# jd9_redraw.net
KiCad netlist of a schematic drawn in EAGLE
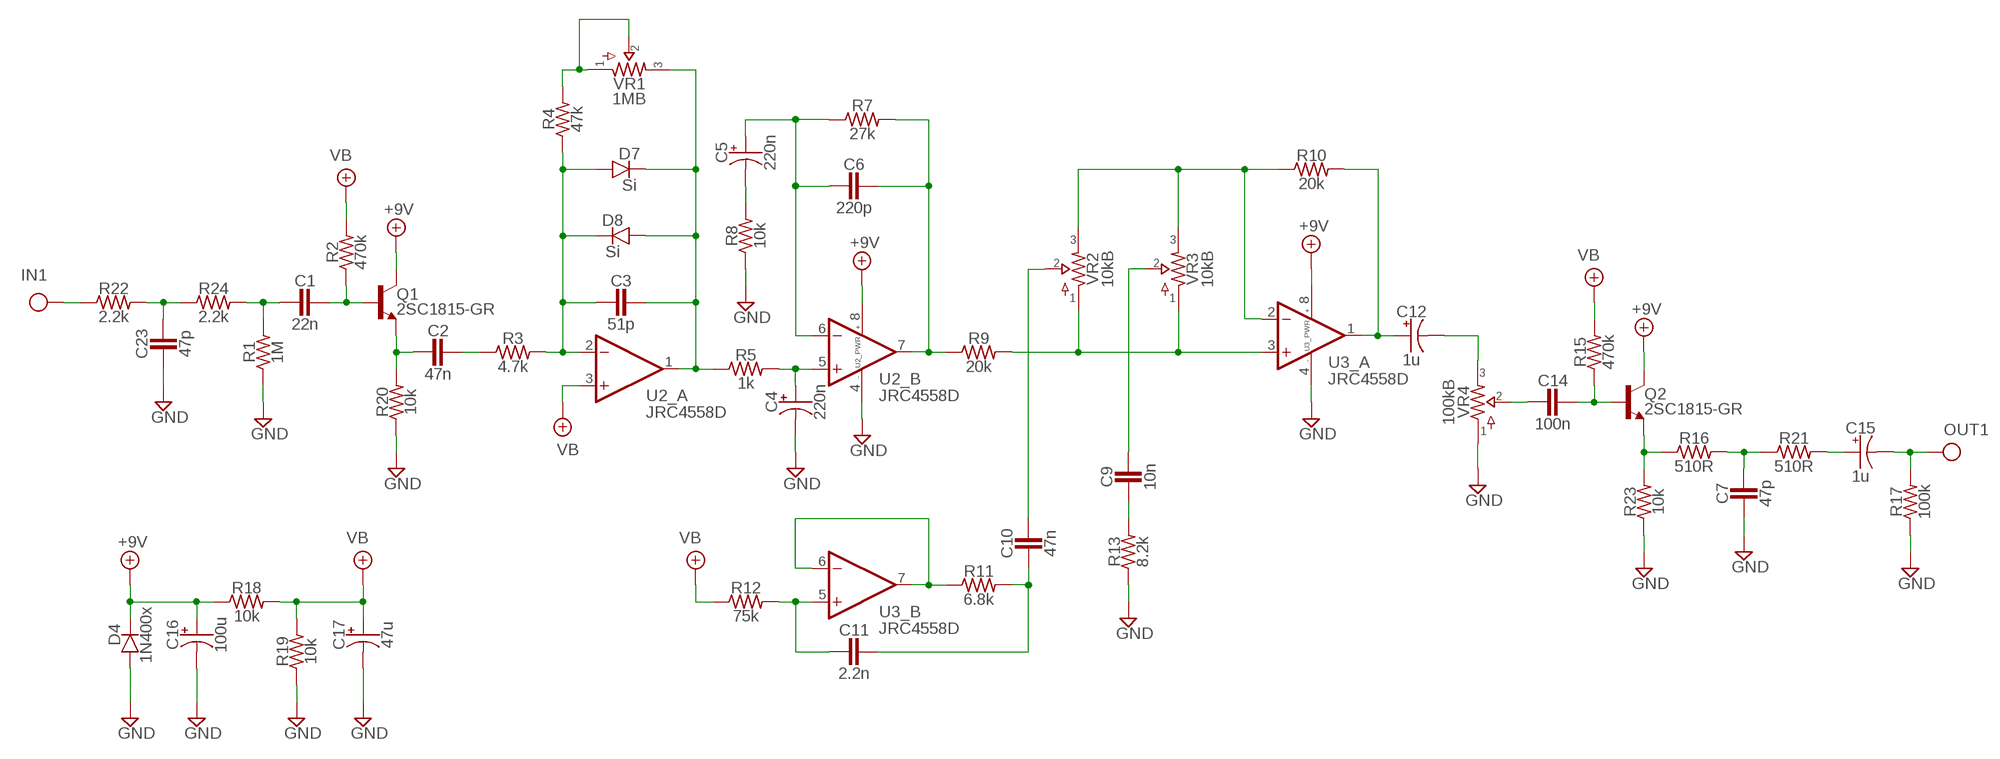
[diagram p0: schematic, sheet 1]

(export (version "E")
  (design (tool "Eeschema 10.0.6"))
  (components
    (comp (ref "C1")
      (value "22n")
      (footprint "eagle-import:BOX_SMALL")
      (libsource (lib "eagle-import") (part "CER/FILMBOX.1"))
    )
    (comp (ref "C2")
      (value "47n")
      (footprint "eagle-import:BOX_SMALL")
      (libsource (lib "eagle-import") (part "CER/FILMBOX.1"))
    )
    (comp (ref "C3")
      (value "51p")
      (footprint "eagle-import:BOX_SMALL")
      (libsource (lib "eagle-import") (part "CER/FILMBOX.1"))
    )
    (comp (ref "C4")
      (value "220n")
      (footprint "eagle-import:050_020")
      (libsource (lib "eagle-import") (part "0500"))
    )
    (comp (ref "C5")
      (value "220n")
      (footprint "eagle-import:050_020")
      (libsource (lib "eagle-import") (part "0500"))
    )
    (comp (ref "C6")
      (value "220p")
      (footprint "eagle-import:BOX_SMALL")
      (libsource (lib "eagle-import") (part "CER/FILMBOX.1"))
    )
    (comp (ref "C7")
      (value "47p")
      (footprint "eagle-import:BOX_SMALL")
      (libsource (lib "eagle-import") (part "CER/FILMBOX.1"))
    )
    (comp (ref "C9")
      (value "10n")
      (footprint "eagle-import:BOX_SMALL")
      (libsource (lib "eagle-import") (part "CER/FILMBOX.1"))
    )
    (comp (ref "C10")
      (value "47n")
      (footprint "eagle-import:BOX_SMALL")
      (libsource (lib "eagle-import") (part "CER/FILMBOX.1"))
    )
    (comp (ref "C11")
      (value "2.2n")
      (footprint "eagle-import:BOX_SMALL")
      (libsource (lib "eagle-import") (part "CER/FILMBOX.1"))
    )
    (comp (ref "C12")
      (value "1u")
      (footprint "eagle-import:050_020")
      (libsource (lib "eagle-import") (part "0500"))
    )
    (comp (ref "C14")
      (value "100n")
      (footprint "eagle-import:BOX_SMALL")
      (libsource (lib "eagle-import") (part "CER/FILMBOX.1"))
    )
    (comp (ref "C15")
      (value "1u")
      (footprint "eagle-import:050_020")
      (libsource (lib "eagle-import") (part "0500"))
    )
    (comp (ref "C16")
      (value "100u")
      (footprint "eagle-import:050_020")
      (libsource (lib "eagle-import") (part "0500"))
    )
    (comp (ref "C17")
      (value "47u")
      (footprint "eagle-import:050_020")
      (libsource (lib "eagle-import") (part "0500"))
    )
    (comp (ref "C23")
      (value "47p")
      (footprint "eagle-import:BOX_SMALL")
      (libsource (lib "eagle-import") (part "CER/FILMBOX.1"))
    )
    (comp (ref "D4")
      (value "1N400x")
      (footprint "eagle-import:DO41-2")
      (libsource (lib "eagle-import") (part "DO41.2"))
    )
    (comp (ref "D7")
      (value "Si")
      (footprint "eagle-import:DO35-2")
      (libsource (lib "eagle-import") (part "DO35.2"))
    )
    (comp (ref "D8")
      (value "Si")
      (footprint "eagle-import:DO35-2")
      (libsource (lib "eagle-import") (part "DO35.2"))
    )
    (comp (ref "Q1")
      (value "2SC1815-GR")
      (footprint "eagle-import:TO92-")
      (libsource (lib "eagle-import") (part "2N3904"))
    )
    (comp (ref "Q2")
      (value "2SC1815-GR")
      (footprint "eagle-import:TO92-")
      (libsource (lib "eagle-import") (part "2N3904"))
    )
    (comp (ref "R1")
      (value "1M")
      (footprint "eagle-import:R0207_3")
      (libsource (lib "eagle-import") (part "R_.3B"))
    )
    (comp (ref "R2")
      (value "470k")
      (footprint "eagle-import:R0207_3")
      (libsource (lib "eagle-import") (part "R_.3B"))
    )
    (comp (ref "R3")
      (value "4.7k")
      (footprint "eagle-import:R0207_3")
      (libsource (lib "eagle-import") (part "R_.3B"))
    )
    (comp (ref "R4")
      (value "47k")
      (footprint "eagle-import:R0207_3")
      (libsource (lib "eagle-import") (part "R_.3B"))
    )
    (comp (ref "R5")
      (value "1k")
      (footprint "eagle-import:R0207_3")
      (libsource (lib "eagle-import") (part "R_.3B"))
    )
    (comp (ref "R7")
      (value "27k")
      (footprint "eagle-import:R0207_3")
      (libsource (lib "eagle-import") (part "R_.3B"))
    )
    (comp (ref "R8")
      (value "10k")
      (footprint "eagle-import:R0207_3")
      (libsource (lib "eagle-import") (part "R_.3B"))
    )
    (comp (ref "R9")
      (value "20k")
      (footprint "eagle-import:R0207_3")
      (libsource (lib "eagle-import") (part "R_.3B"))
    )
    (comp (ref "R10")
      (value "20k")
      (footprint "eagle-import:R0207_3")
      (libsource (lib "eagle-import") (part "R_.3B"))
    )
    (comp (ref "R11")
      (value "6.8k")
      (footprint "eagle-import:R0207_3")
      (libsource (lib "eagle-import") (part "R_.3B"))
    )
    (comp (ref "R12")
      (value "75k")
      (footprint "eagle-import:R0207_3")
      (libsource (lib "eagle-import") (part "R_.3B"))
    )
    (comp (ref "R13")
      (value "8.2k")
      (footprint "eagle-import:R0207_3")
      (libsource (lib "eagle-import") (part "R_.3B"))
    )
    (comp (ref "R15")
      (value "470k")
      (footprint "eagle-import:R0207_3")
      (libsource (lib "eagle-import") (part "R_.3B"))
    )
    (comp (ref "R16")
      (value "510R")
      (footprint "eagle-import:R0207_3")
      (libsource (lib "eagle-import") (part "R_.3B"))
    )
    (comp (ref "R17")
      (value "100k")
      (footprint "eagle-import:R0207_3")
      (libsource (lib "eagle-import") (part "R_.3B"))
    )
    (comp (ref "R18")
      (value "10k")
      (footprint "eagle-import:R0207_3")
      (libsource (lib "eagle-import") (part "R_.3B"))
    )
    (comp (ref "R19")
      (value "10k")
      (footprint "eagle-import:R0207_3")
      (libsource (lib "eagle-import") (part "R_.3B"))
    )
    (comp (ref "R20")
      (value "10k")
      (footprint "eagle-import:R0207_3")
      (libsource (lib "eagle-import") (part "R_.3B"))
    )
    (comp (ref "R21")
      (value "510R")
      (footprint "eagle-import:R0207_3")
      (libsource (lib "eagle-import") (part "R_.3B"))
    )
    (comp (ref "R22")
      (value "2.2k")
      (footprint "eagle-import:R0207_3")
      (libsource (lib "eagle-import") (part "R_.3B"))
    )
    (comp (ref "R23")
      (value "10k")
      (footprint "eagle-import:R0207_3")
      (libsource (lib "eagle-import") (part "R_.3B"))
    )
    (comp (ref "R24")
      (value "2.2k")
      (footprint "eagle-import:R0207_3")
      (libsource (lib "eagle-import") (part "R_.3B"))
    )
    (comp (ref "U2")
      (value "JRC4558D")
      (footprint "eagle-import:DIL0")
      (libsource (lib "eagle-import") (part "DUALTH"))
    )
    (comp (ref "U3")
      (value "JRC4558D")
      (footprint "eagle-import:DIL0")
      (libsource (lib "eagle-import") (part "DUALTH"))
    )
    (comp (ref "VR1")
      (value "1MB")
      (footprint "eagle-import:16MM")
      (libsource (lib "eagle-import") (part "POTS16MM"))
    )
    (comp (ref "VR2")
      (value "10kB")
      (footprint "eagle-import:16MM")
      (libsource (lib "eagle-import") (part "POTS16MM"))
    )
    (comp (ref "VR3")
      (value "10kB")
      (footprint "eagle-import:16MM")
      (libsource (lib "eagle-import") (part "POTS16MM"))
    )
    (comp (ref "VR4")
      (value "100kB")
      (footprint "eagle-import:16MM")
      (libsource (lib "eagle-import") (part "POTS16MM"))
    )
  )
  (nets
    (net (code "1") (name "+9V") (class "Default")
      (node (ref "C16") (pin "+") (pinfunction "+_+") (pintype "passive"))
      (node (ref "D4") (pin "C") (pinfunction "C_C") (pintype "passive"))
      (node (ref "Q1") (pin "1") (pinfunction "C_1") (pintype "passive"))
      (node (ref "Q2") (pin "1") (pinfunction "C_1") (pintype "passive"))
      (node (ref "R18") (pin "1") (pinfunction "1_1") (pintype "passive"))
      (node (ref "U2") (pin "8") (pinfunction "V+_8") (pintype "power_in"))
      (node (ref "U3") (pin "8") (pinfunction "V+_8") (pintype "power_in"))
    )
    (net (code "2") (name "GND") (class "Default")
      (node (ref "C16") (pin "-") (pinfunction "-_-") (pintype "passive"))
      (node (ref "C17") (pin "-") (pinfunction "-_-") (pintype "passive"))
      (node (ref "C23") (pin "2") (pinfunction "2_2") (pintype "passive"))
      (node (ref "C4") (pin "-") (pinfunction "-_-") (pintype "passive"))
      (node (ref "C7") (pin "2") (pinfunction "2_2") (pintype "passive"))
      (node (ref "D4") (pin "A") (pinfunction "A_A") (pintype "passive"))
      (node (ref "R1") (pin "1") (pinfunction "1_1") (pintype "passive"))
      (node (ref "R13") (pin "1") (pinfunction "1_1") (pintype "passive"))
      (node (ref "R17") (pin "1") (pinfunction "1_1") (pintype "passive"))
      (node (ref "R19") (pin "1") (pinfunction "1_1") (pintype "passive"))
      (node (ref "R20") (pin "1") (pinfunction "1_1") (pintype "passive"))
      (node (ref "R23") (pin "1") (pinfunction "1_1") (pintype "passive"))
      (node (ref "R8") (pin "1") (pinfunction "1_1") (pintype "passive"))
      (node (ref "U2") (pin "4") (pinfunction "V-_4") (pintype "power_in"))
      (node (ref "U3") (pin "4") (pinfunction "V-_4") (pintype "power_in"))
      (node (ref "VR4") (pin "1") (pinfunction "1_1") (pintype "passive"))
    )
    (net (code "3") (name "IN") (class "Default")
      (node (ref "R22") (pin "1") (pinfunction "1_1") (pintype "passive"))
    )
    (net (code "4") (name "Net-(C1-Pad2)") (class "Default")
      (node (ref "C1") (pin "2") (pinfunction "2_2") (pintype "passive"))
      (node (ref "R1") (pin "2") (pinfunction "2_2") (pintype "passive"))
      (node (ref "R24") (pin "2") (pinfunction "2_2") (pintype "passive"))
    )
    (net (code "5") (name "Net-(C2-Pad1)") (class "Default")
      (node (ref "C2") (pin "1") (pinfunction "1_1") (pintype "passive"))
      (node (ref "R3") (pin "1") (pinfunction "1_1") (pintype "passive"))
    )
    (net (code "6") (name "Net-(C5-Pad-)") (class "Default")
      (node (ref "C5") (pin "-") (pinfunction "-_-") (pintype "passive"))
      (node (ref "R8") (pin "2") (pinfunction "2_2") (pintype "passive"))
    )
    (net (code "7") (name "Net-(C7-Pad1)") (class "Default")
      (node (ref "C7") (pin "1") (pinfunction "1_1") (pintype "passive"))
      (node (ref "R16") (pin "2") (pinfunction "2_2") (pintype "passive"))
      (node (ref "R21") (pin "1") (pinfunction "1_1") (pintype "passive"))
    )
    (net (code "8") (name "Net-(C9-Pad1)") (class "Default")
      (node (ref "C9") (pin "1") (pinfunction "1_1") (pintype "passive"))
      (node (ref "VR3") (pin "2") (pinfunction "2_2") (pintype "passive"))
    )
    (net (code "9") (name "Net-(C9-Pad2)") (class "Default")
      (node (ref "C9") (pin "2") (pinfunction "2_2") (pintype "passive"))
      (node (ref "R13") (pin "2") (pinfunction "2_2") (pintype "passive"))
    )
    (net (code "10") (name "Net-(C10-Pad1)") (class "Default")
      (node (ref "C10") (pin "1") (pinfunction "1_1") (pintype "passive"))
      (node (ref "VR2") (pin "2") (pinfunction "2_2") (pintype "passive"))
    )
    (net (code "11") (name "Net-(C10-Pad2)") (class "Default")
      (node (ref "C10") (pin "2") (pinfunction "2_2") (pintype "passive"))
      (node (ref "C11") (pin "1") (pinfunction "1_1") (pintype "passive"))
      (node (ref "R11") (pin "2") (pinfunction "2_2") (pintype "passive"))
    )
    (net (code "12") (name "Net-(C12-Pad-)") (class "Default")
      (node (ref "C12") (pin "-") (pinfunction "-_-") (pintype "passive"))
      (node (ref "VR4") (pin "3") (pinfunction "3_3") (pintype "passive"))
    )
    (net (code "13") (name "Net-(C14-Pad2)") (class "Default")
      (node (ref "C14") (pin "2") (pinfunction "2_2") (pintype "passive"))
      (node (ref "VR4") (pin "2") (pinfunction "2_2") (pintype "passive"))
    )
    (net (code "14") (name "Net-(C15-Pad+)") (class "Default")
      (node (ref "C15") (pin "+") (pinfunction "+_+") (pintype "passive"))
      (node (ref "R21") (pin "2") (pinfunction "2_2") (pintype "passive"))
    )
    (net (code "15") (name "Net-(C23-Pad1)") (class "Default")
      (node (ref "C23") (pin "1") (pinfunction "1_1") (pintype "passive"))
      (node (ref "R22") (pin "2") (pinfunction "2_2") (pintype "passive"))
      (node (ref "R24") (pin "1") (pinfunction "1_1") (pintype "passive"))
    )
    (net (code "16") (name "Net-(Q1-B)") (class "Default")
      (node (ref "C1") (pin "1") (pinfunction "1_1") (pintype "passive"))
      (node (ref "Q1") (pin "2") (pinfunction "B_2") (pintype "passive"))
      (node (ref "R2") (pin "1") (pinfunction "1_1") (pintype "passive"))
    )
    (net (code "17") (name "Net-(Q1-E)") (class "Default")
      (node (ref "C2") (pin "2") (pinfunction "2_2") (pintype "passive"))
      (node (ref "Q1") (pin "3") (pinfunction "E_3") (pintype "passive"))
      (node (ref "R20") (pin "2") (pinfunction "2_2") (pintype "passive"))
    )
    (net (code "18") (name "Net-(Q2-B)") (class "Default")
      (node (ref "C14") (pin "1") (pinfunction "1_1") (pintype "passive"))
      (node (ref "Q2") (pin "2") (pinfunction "B_2") (pintype "passive"))
      (node (ref "R15") (pin "1") (pinfunction "1_1") (pintype "passive"))
    )
    (net (code "19") (name "Net-(Q2-E)") (class "Default")
      (node (ref "Q2") (pin "3") (pinfunction "E_3") (pintype "passive"))
      (node (ref "R16") (pin "1") (pinfunction "1_1") (pintype "passive"))
      (node (ref "R23") (pin "2") (pinfunction "2_2") (pintype "passive"))
    )
    (net (code "20") (name "Net-(R4-Pad2)") (class "Default")
      (node (ref "R4") (pin "2") (pinfunction "2_2") (pintype "passive"))
      (node (ref "VR1") (pin "1") (pinfunction "1_1") (pintype "passive"))
      (node (ref "VR1") (pin "2") (pinfunction "2_2") (pintype "passive"))
    )
    (net (code "21") (name "Net-(U2A--IN)") (class "Default")
      (node (ref "C3") (pin "2") (pinfunction "2_2") (pintype "passive"))
      (node (ref "D7") (pin "A") (pinfunction "A_A") (pintype "passive"))
      (node (ref "D8") (pin "C") (pinfunction "C_C") (pintype "passive"))
      (node (ref "R3") (pin "2") (pinfunction "2_2") (pintype "passive"))
      (node (ref "R4") (pin "1") (pinfunction "1_1") (pintype "passive"))
      (node (ref "U2") (pin "2") (pinfunction "-IN_2") (pintype "input"))
    )
    (net (code "22") (name "Net-(U2A-OUT)") (class "Default")
      (node (ref "C3") (pin "1") (pinfunction "1_1") (pintype "passive"))
      (node (ref "D7") (pin "C") (pinfunction "C_C") (pintype "passive"))
      (node (ref "D8") (pin "A") (pinfunction "A_A") (pintype "passive"))
      (node (ref "R5") (pin "1") (pinfunction "1_1") (pintype "passive"))
      (node (ref "U2") (pin "1") (pinfunction "OUT_1") (pintype "output"))
      (node (ref "VR1") (pin "3") (pinfunction "3_3") (pintype "passive"))
    )
    (net (code "23") (name "Net-(U2B-+IN)") (class "Default")
      (node (ref "C4") (pin "+") (pinfunction "+_+") (pintype "passive"))
      (node (ref "R5") (pin "2") (pinfunction "2_2") (pintype "passive"))
      (node (ref "U2") (pin "5") (pinfunction "+IN_5") (pintype "input"))
    )
    (net (code "24") (name "Net-(U2B--IN)") (class "Default")
      (node (ref "C5") (pin "+") (pinfunction "+_+") (pintype "passive"))
      (node (ref "C6") (pin "2") (pinfunction "2_2") (pintype "passive"))
      (node (ref "R7") (pin "1") (pinfunction "1_1") (pintype "passive"))
      (node (ref "U2") (pin "6") (pinfunction "-IN_6") (pintype "input"))
    )
    (net (code "25") (name "Net-(U2B-OUT)") (class "Default")
      (node (ref "C6") (pin "1") (pinfunction "1_1") (pintype "passive"))
      (node (ref "R7") (pin "2") (pinfunction "2_2") (pintype "passive"))
      (node (ref "R9") (pin "1") (pinfunction "1_1") (pintype "passive"))
      (node (ref "U2") (pin "7") (pinfunction "OUT_7") (pintype "output"))
    )
    (net (code "26") (name "Net-(U3A-+IN)") (class "Default")
      (node (ref "R9") (pin "2") (pinfunction "2_2") (pintype "passive"))
      (node (ref "U3") (pin "3") (pinfunction "+IN_3") (pintype "input"))
      (node (ref "VR2") (pin "1") (pinfunction "1_1") (pintype "passive"))
      (node (ref "VR3") (pin "1") (pinfunction "1_1") (pintype "passive"))
    )
    (net (code "27") (name "Net-(U3A--IN)") (class "Default")
      (node (ref "R10") (pin "1") (pinfunction "1_1") (pintype "passive"))
      (node (ref "U3") (pin "2") (pinfunction "-IN_2") (pintype "input"))
      (node (ref "VR2") (pin "3") (pinfunction "3_3") (pintype "passive"))
      (node (ref "VR3") (pin "3") (pinfunction "3_3") (pintype "passive"))
    )
    (net (code "28") (name "Net-(U3A-OUT)") (class "Default")
      (node (ref "C12") (pin "+") (pinfunction "+_+") (pintype "passive"))
      (node (ref "R10") (pin "2") (pinfunction "2_2") (pintype "passive"))
      (node (ref "U3") (pin "1") (pinfunction "OUT_1") (pintype "output"))
    )
    (net (code "29") (name "Net-(U3B-+IN)") (class "Default")
      (node (ref "C11") (pin "2") (pinfunction "2_2") (pintype "passive"))
      (node (ref "R12") (pin "2") (pinfunction "2_2") (pintype "passive"))
      (node (ref "U3") (pin "5") (pinfunction "+IN_5") (pintype "input"))
    )
    (net (code "30") (name "Net-(U3B--IN)") (class "Default")
      (node (ref "R11") (pin "1") (pinfunction "1_1") (pintype "passive"))
      (node (ref "U3") (pin "6") (pinfunction "-IN_6") (pintype "input"))
      (node (ref "U3") (pin "7") (pinfunction "OUT_7") (pintype "output"))
    )
    (net (code "31") (name "OUT") (class "Default")
      (node (ref "C15") (pin "-") (pinfunction "-_-") (pintype "passive"))
      (node (ref "R17") (pin "2") (pinfunction "2_2") (pintype "passive"))
    )
    (net (code "32") (name "VB") (class "Default")
      (node (ref "C17") (pin "+") (pinfunction "+_+") (pintype "passive"))
      (node (ref "R12") (pin "1") (pinfunction "1_1") (pintype "passive"))
      (node (ref "R15") (pin "2") (pinfunction "2_2") (pintype "passive"))
      (node (ref "R18") (pin "2") (pinfunction "2_2") (pintype "passive"))
      (node (ref "R19") (pin "2") (pinfunction "2_2") (pintype "passive"))
      (node (ref "R2") (pin "2") (pinfunction "2_2") (pintype "passive"))
      (node (ref "U2") (pin "3") (pinfunction "+IN_3") (pintype "input"))
    )
  )
)
